# UART-Adapter.net
KiCad netlist of a schematic drawn in EAGLE
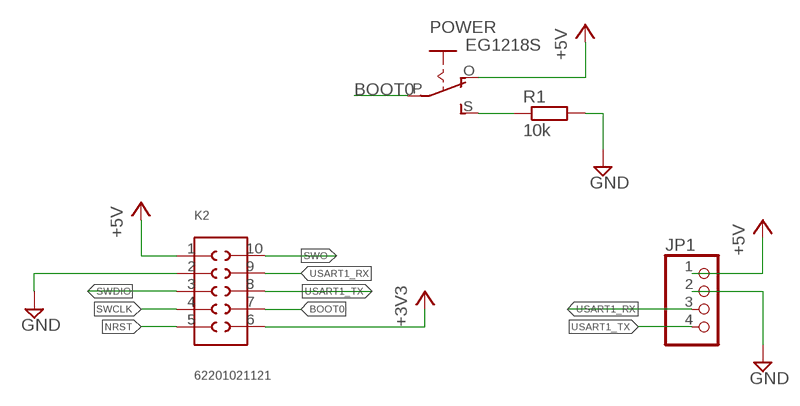
[diagram p0: schematic, sheet 1]

(export (version "E")
  (design (tool "Eeschema 10.0.6"))
  (components
    (comp (ref "JP1")
      (value "PINHD-1X4")
      (footprint "eagle-import:1X04")
      (libsource (lib "eagle-import") (part "PINHD-1X4"))
    )
    (comp (ref "K2")
      (value "62201021121")
      (footprint "eagle-import:62201021121")
      (libsource (lib "eagle-import") (part "62201021121"))
    )
    (comp (ref "POWER")
      (value "EG1218S")
      (footprint "eagle-import:EG1218")
      (fields (field (name "MF") "E-Switch") (field (name "MP") "EG1218"))
      (libsource (lib "eagle-import") (part "EG1218S"))
    )
    (comp (ref "R1")
      (value "10k")
      (footprint "eagle-import:R0603")
      (libsource (lib "eagle-import") (part "R-EU_R0603"))
    )
  )
  (nets
    (net (code "1") (name "+3V3") (class "Default")
      (node (ref "K2") (pin "6") (pinfunction "6_6") (pintype "passive"))
    )
    (net (code "2") (name "+5V") (class "Default")
      (node (ref "JP1") (pin "1") (pinfunction "1_1") (pintype "passive"))
      (node (ref "K2") (pin "1") (pinfunction "1_1") (pintype "passive"))
      (node (ref "POWER") (pin "O") (pinfunction "O_O") (pintype "passive"))
    )
    (net (code "3") (name "BOOT0") (class "Default")
      (node (ref "K2") (pin "7") (pinfunction "7_7") (pintype "passive"))
      (node (ref "POWER") (pin "P") (pinfunction "P_P") (pintype "passive"))
    )
    (net (code "4") (name "GND") (class "Default")
      (node (ref "JP1") (pin "2") (pinfunction "2_2") (pintype "passive"))
      (node (ref "K2") (pin "2") (pinfunction "2_2") (pintype "passive"))
      (node (ref "R1") (pin "2") (pinfunction "2_2") (pintype "passive"))
    )
    (net (code "5") (name "NRST") (class "Default")
      (node (ref "K2") (pin "5") (pinfunction "5_5") (pintype "passive"))
    )
    (net (code "6") (name "Net-(POWER-PadS)") (class "Default")
      (node (ref "POWER") (pin "S") (pinfunction "S_S") (pintype "passive"))
      (node (ref "R1") (pin "1") (pinfunction "1_1") (pintype "passive"))
    )
    (net (code "7") (name "SWCLK") (class "Default")
      (node (ref "K2") (pin "4") (pinfunction "4_4") (pintype "passive"))
    )
    (net (code "8") (name "SWDIO") (class "Default")
      (node (ref "K2") (pin "3") (pinfunction "3_3") (pintype "passive"))
    )
    (net (code "9") (name "SWO") (class "Default")
      (node (ref "K2") (pin "10") (pinfunction "10_10") (pintype "passive"))
    )
    (net (code "10") (name "USART1_RX") (class "Default")
      (node (ref "JP1") (pin "3") (pinfunction "3_3") (pintype "passive"))
      (node (ref "K2") (pin "9") (pinfunction "9_9") (pintype "passive"))
    )
    (net (code "11") (name "USART1_TX") (class "Default")
      (node (ref "JP1") (pin "4") (pinfunction "4_4") (pintype "passive"))
      (node (ref "K2") (pin "8") (pinfunction "8_8") (pintype "passive"))
    )
  )
)
